# MainBoard.net
KiCad netlist of a schematic drawn in EAGLE
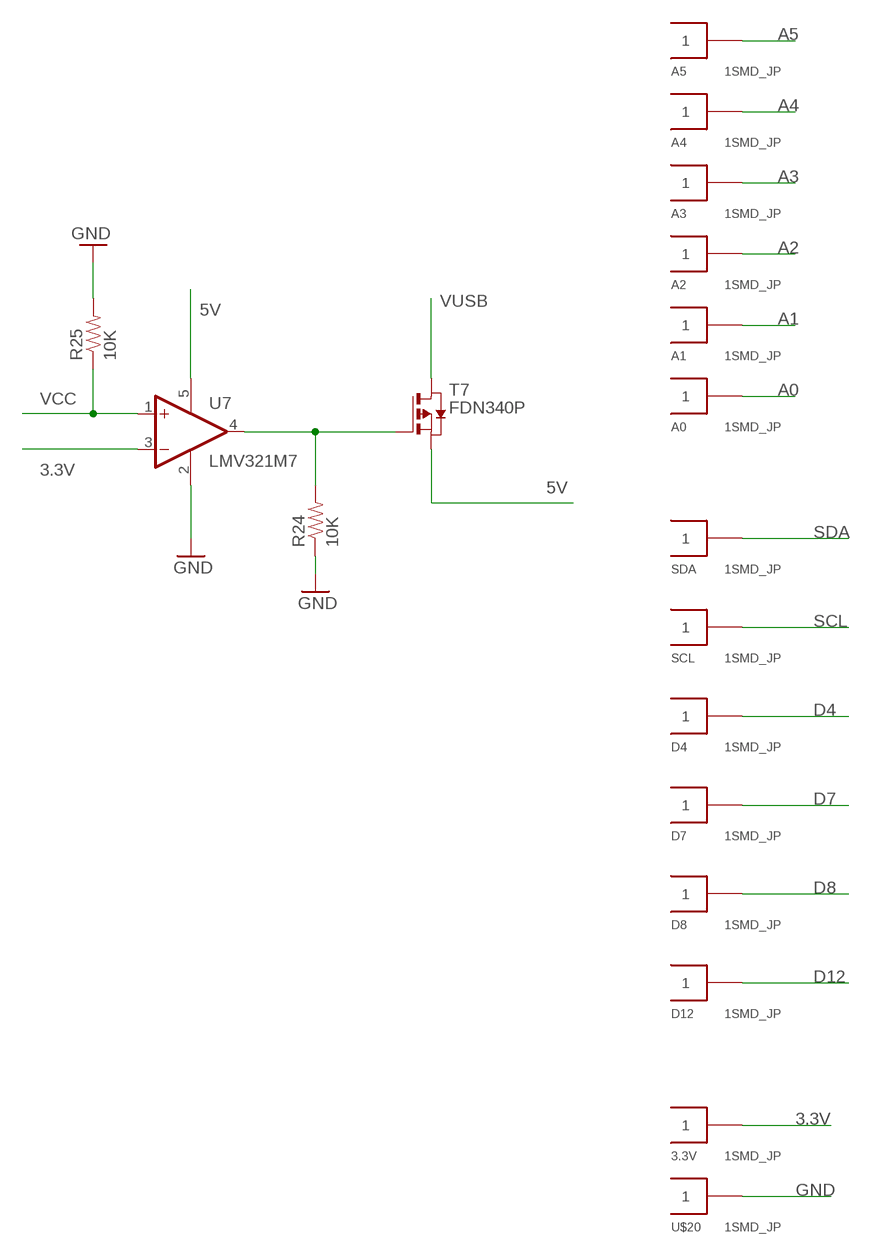
[diagram p0: schematic, sheet 1, part 1 of 2]
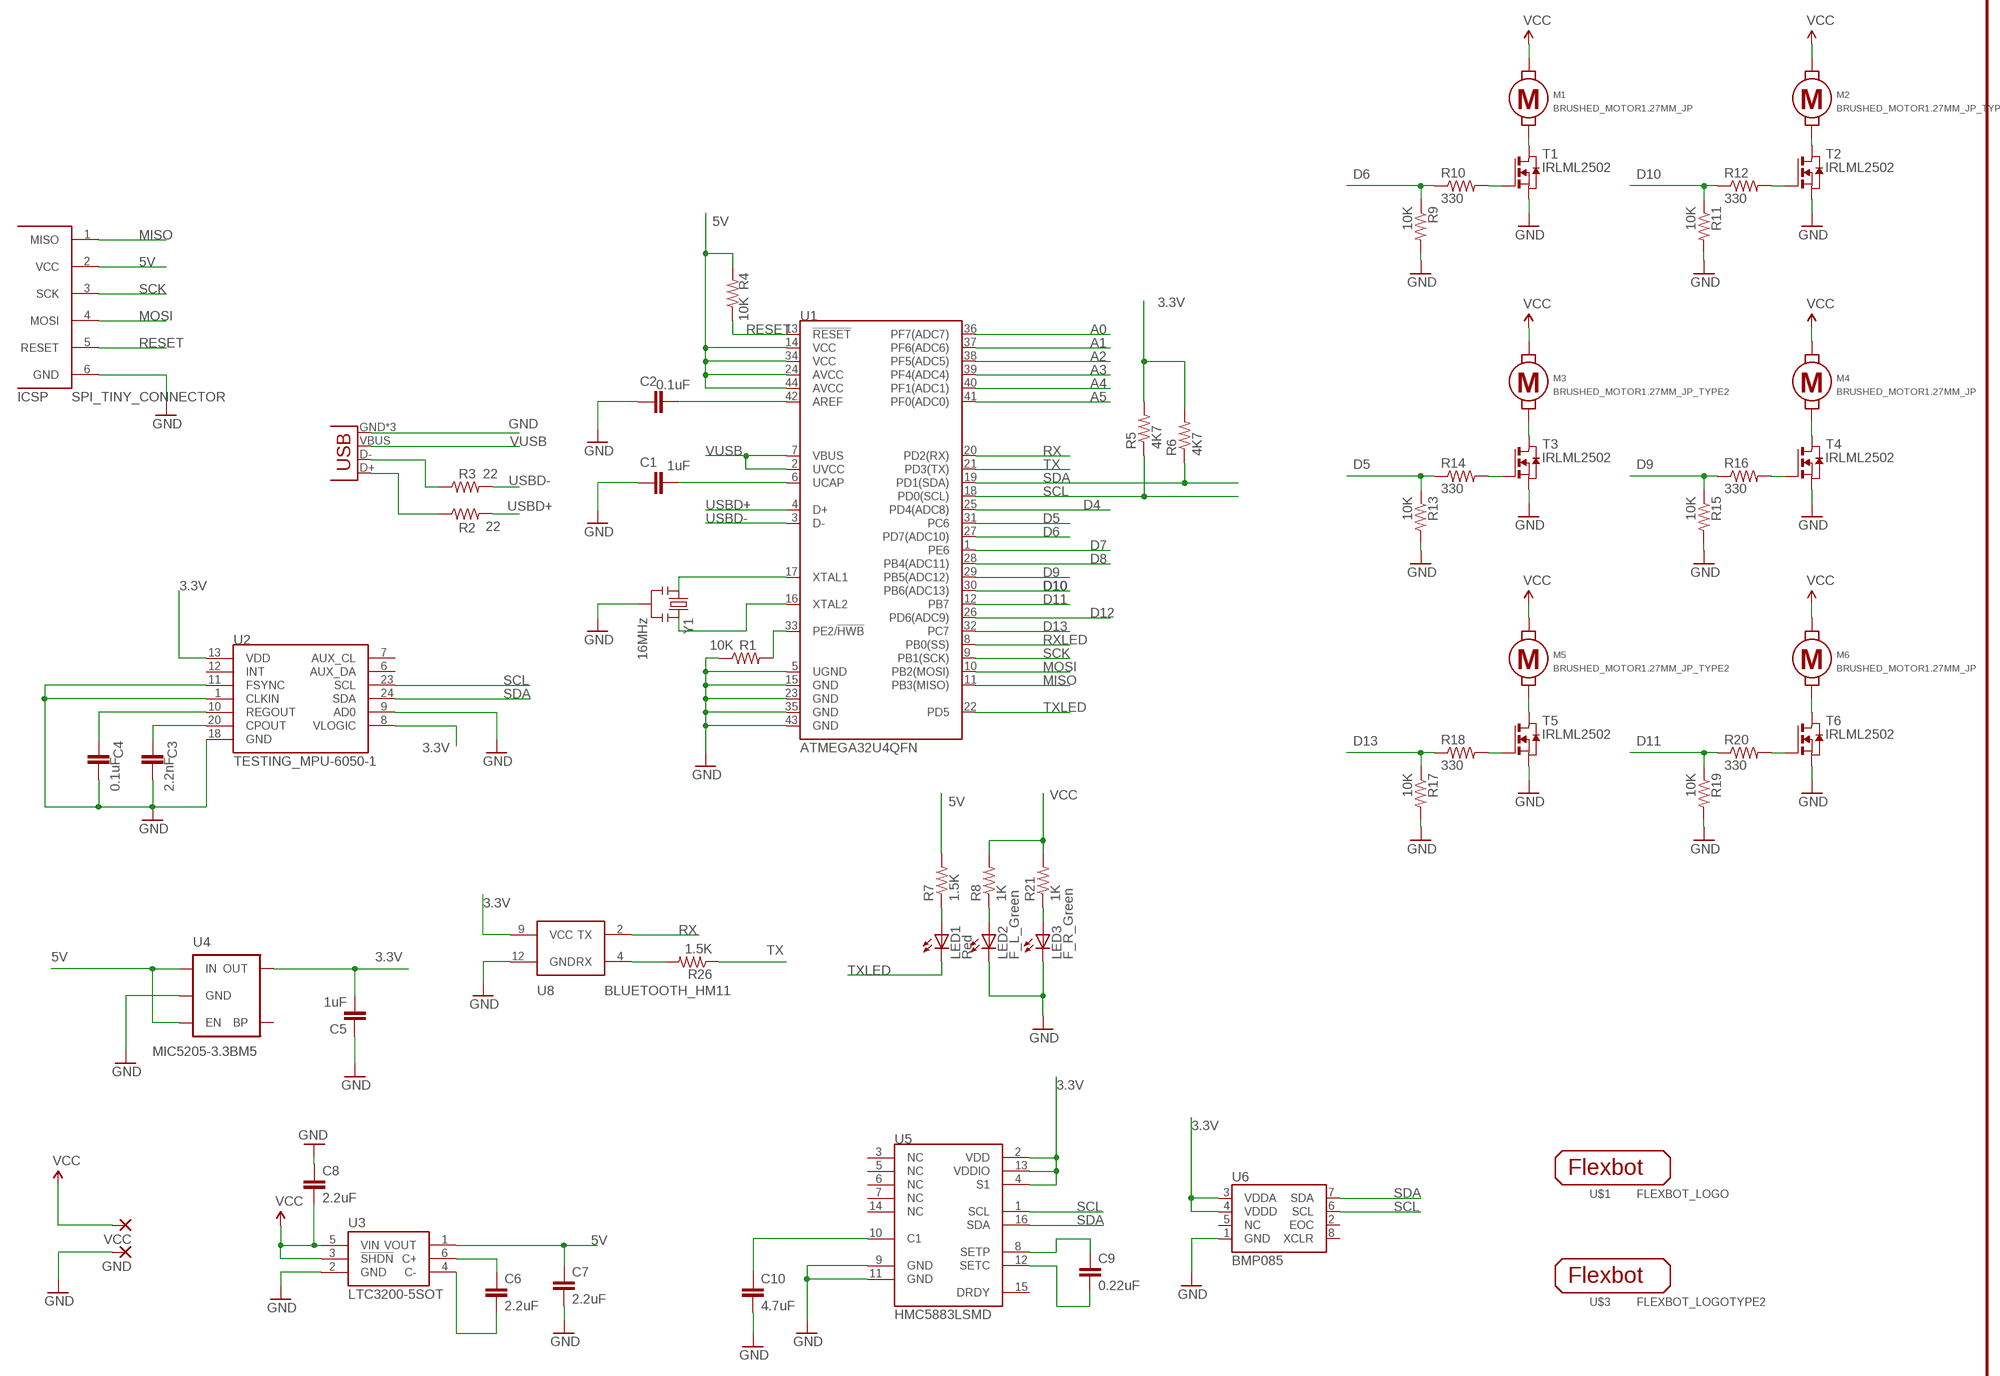
[diagram p1: schematic, sheet 1, part 2 of 2]

(export (version "E")
  (design (tool "Eeschema 10.0.6"))
  (components
    (comp (ref "3.3V")
      (value "1SMD_JP")
      (footprint "eagle-import:1SMD")
      (libsource (lib "eagle-import") (part "1SMD_JP"))
    )
    (comp (ref "A0")
      (value "1SMD_JP")
      (footprint "eagle-import:1SMD")
      (libsource (lib "eagle-import") (part "1SMD_JP"))
    )
    (comp (ref "A1")
      (value "1SMD_JP")
      (footprint "eagle-import:1SMD")
      (libsource (lib "eagle-import") (part "1SMD_JP"))
    )
    (comp (ref "A2")
      (value "1SMD_JP")
      (footprint "eagle-import:1SMD")
      (libsource (lib "eagle-import") (part "1SMD_JP"))
    )
    (comp (ref "A3")
      (value "1SMD_JP")
      (footprint "eagle-import:1SMD")
      (libsource (lib "eagle-import") (part "1SMD_JP"))
    )
    (comp (ref "A4")
      (value "1SMD_JP")
      (footprint "eagle-import:1SMD")
      (libsource (lib "eagle-import") (part "1SMD_JP"))
    )
    (comp (ref "A5")
      (value "1SMD_JP")
      (footprint "eagle-import:1SMD")
      (libsource (lib "eagle-import") (part "1SMD_JP"))
    )
    (comp (ref "C1")
      (value "1uF")
      (footprint "eagle-import:0402-CAP")
      (libsource (lib "eagle-import") (part "CAP0402-CAP"))
    )
    (comp (ref "C2")
      (value "0.1uF")
      (footprint "eagle-import:0402-CAP")
      (libsource (lib "eagle-import") (part "CAP0402-CAP"))
    )
    (comp (ref "C3")
      (value "2.2nF")
      (footprint "eagle-import:0402-CAP")
      (libsource (lib "eagle-import") (part "CAP0402-CAP"))
    )
    (comp (ref "C4")
      (value "0.1uF")
      (footprint "eagle-import:0402-CAP")
      (libsource (lib "eagle-import") (part "CAP0402-CAP"))
    )
    (comp (ref "C5")
      (value "1uF")
      (footprint "eagle-import:0402-CAP")
      (libsource (lib "eagle-import") (part "CAP0402-CAP"))
    )
    (comp (ref "C6")
      (value "2.2uF")
      (footprint "eagle-import:0603-CAP")
      (libsource (lib "eagle-import") (part "CAP0603-CAP"))
    )
    (comp (ref "C7")
      (value "2.2uF")
      (footprint "eagle-import:0603-CAP")
      (libsource (lib "eagle-import") (part "CAP0603-CAP"))
    )
    (comp (ref "C8")
      (value "2.2uF")
      (footprint "eagle-import:0603-CAP")
      (libsource (lib "eagle-import") (part "CAP0603-CAP"))
    )
    (comp (ref "C9")
      (value "0.22uF")
      (footprint "eagle-import:0402-CAP")
      (libsource (lib "eagle-import") (part "CAP0402-CAP"))
    )
    (comp (ref "C10")
      (value "4.7uF")
      (footprint "eagle-import:0603-CAP")
      (libsource (lib "eagle-import") (part "CAP0603-CAP"))
    )
    (comp (ref "D4")
      (value "1SMD_JP")
      (footprint "eagle-import:1SMD")
      (libsource (lib "eagle-import") (part "1SMD_JP"))
    )
    (comp (ref "D7")
      (value "1SMD_JP")
      (footprint "eagle-import:1SMD")
      (libsource (lib "eagle-import") (part "1SMD_JP"))
    )
    (comp (ref "D8")
      (value "1SMD_JP")
      (footprint "eagle-import:1SMD")
      (libsource (lib "eagle-import") (part "1SMD_JP"))
    )
    (comp (ref "D12")
      (value "1SMD_JP")
      (footprint "eagle-import:1SMD")
      (libsource (lib "eagle-import") (part "1SMD_JP"))
    )
    (comp (ref "GND")
      (value "2,15/1,0")
      (footprint "eagle-import:2,15_1,0")
      (libsource (lib "eagle-import") (part "2,15/1,0"))
    )
    (comp (ref "ICSP")
      (value "SPI_TINY_CONNECTOR")
      (footprint "eagle-import:AVR_ISP_TINY_CONNECTOR_NO_BORDER")
      (libsource (lib "eagle-import") (part "AVR_ISP_TINY_CONNECTORAVR_ISP_TINY_CONNCTOR_NO_BORDER"))
    )
    (comp (ref "JP1")
      (value "USB-MICROB")
      (footprint "eagle-import:USB-MICROB")
      (libsource (lib "eagle-import") (part "USB-MICROB"))
    )
    (comp (ref "LED1")
      (value "Red")
      (footprint "eagle-import:CHIPLED_0603")
      (libsource (lib "eagle-import") (part "LEDCHIPLED_0603"))
    )
    (comp (ref "LED2")
      (value "F_L_Green")
      (footprint "eagle-import:CHIPLED_0603")
      (libsource (lib "eagle-import") (part "LEDCHIPLED_0603"))
    )
    (comp (ref "LED3")
      (value "F_R_Green")
      (footprint "eagle-import:CHIPLED_0603")
      (libsource (lib "eagle-import") (part "LEDCHIPLED_0603"))
    )
    (comp (ref "M1")
      (value "BRUSHED_MOTOR1.27MM_JP")
      (footprint "eagle-import:BRUSHED_MOTOR_1.27MM_JP")
      (libsource (lib "eagle-import") (part "BRUSHED_MOTOR1.27MM_JP"))
    )
    (comp (ref "M2")
      (value "BRUSHED_MOTOR1.27MM_JP_TYPE2")
      (footprint "eagle-import:BRUSHED_MOTOR_1.27MM_JP_TYPE2")
      (libsource (lib "eagle-import") (part "BRUSHED_MOTOR1.27MM_JP_TYPE2"))
    )
    (comp (ref "M3")
      (value "BRUSHED_MOTOR1.27MM_JP_TYPE2")
      (footprint "eagle-import:BRUSHED_MOTOR_1.27MM_JP_TYPE2")
      (libsource (lib "eagle-import") (part "BRUSHED_MOTOR1.27MM_JP_TYPE2"))
    )
    (comp (ref "M4")
      (value "BRUSHED_MOTOR1.27MM_JP")
      (footprint "eagle-import:BRUSHED_MOTOR_1.27MM_JP")
      (libsource (lib "eagle-import") (part "BRUSHED_MOTOR1.27MM_JP"))
    )
    (comp (ref "M5")
      (value "BRUSHED_MOTOR1.27MM_JP_TYPE2")
      (footprint "eagle-import:BRUSHED_MOTOR_1.27MM_JP_TYPE2")
      (libsource (lib "eagle-import") (part "BRUSHED_MOTOR1.27MM_JP_TYPE2"))
    )
    (comp (ref "M6")
      (value "BRUSHED_MOTOR1.27MM_JP")
      (footprint "eagle-import:BRUSHED_MOTOR_1.27MM_JP")
      (libsource (lib "eagle-import") (part "BRUSHED_MOTOR1.27MM_JP"))
    )
    (comp (ref "R1")
      (value "10K")
      (footprint "eagle-import:0402-RES")
      (libsource (lib "eagle-import") (part "RESISTOR0402-RES"))
    )
    (comp (ref "R2")
      (value "22")
      (footprint "eagle-import:0402-RES")
      (libsource (lib "eagle-import") (part "RESISTOR0402-RES"))
    )
    (comp (ref "R3")
      (value "22")
      (footprint "eagle-import:0402-RES")
      (libsource (lib "eagle-import") (part "RESISTOR0402-RES"))
    )
    (comp (ref "R4")
      (value "10K")
      (footprint "eagle-import:0402-RES")
      (libsource (lib "eagle-import") (part "RESISTOR0402-RES"))
    )
    (comp (ref "R5")
      (value "4K7")
      (footprint "eagle-import:0402-RES")
      (libsource (lib "eagle-import") (part "RESISTOR0402-RES"))
    )
    (comp (ref "R6")
      (value "4K7")
      (footprint "eagle-import:0402-RES")
      (libsource (lib "eagle-import") (part "RESISTOR0402-RES"))
    )
    (comp (ref "R7")
      (value "1.5K")
      (footprint "eagle-import:0402-RES")
      (libsource (lib "eagle-import") (part "RESISTOR0402-RES"))
    )
    (comp (ref "R8")
      (value "1K")
      (footprint "eagle-import:0402-RES")
      (libsource (lib "eagle-import") (part "RESISTOR0402-RES"))
    )
    (comp (ref "R9")
      (value "10K")
      (footprint "eagle-import:0402-RES")
      (libsource (lib "eagle-import") (part "RESISTOR0402-RES"))
    )
    (comp (ref "R10")
      (value "330")
      (footprint "eagle-import:0402-RES")
      (libsource (lib "eagle-import") (part "RESISTOR0402-RES"))
    )
    (comp (ref "R11")
      (value "10K")
      (footprint "eagle-import:0402-RES")
      (libsource (lib "eagle-import") (part "RESISTOR0402-RES"))
    )
    (comp (ref "R12")
      (value "330")
      (footprint "eagle-import:0402-RES")
      (libsource (lib "eagle-import") (part "RESISTOR0402-RES"))
    )
    (comp (ref "R13")
      (value "10K")
      (footprint "eagle-import:0402-RES")
      (libsource (lib "eagle-import") (part "RESISTOR0402-RES"))
    )
    (comp (ref "R14")
      (value "330")
      (footprint "eagle-import:0402-RES")
      (libsource (lib "eagle-import") (part "RESISTOR0402-RES"))
    )
    (comp (ref "R15")
      (value "10K")
      (footprint "eagle-import:0402-RES")
      (libsource (lib "eagle-import") (part "RESISTOR0402-RES"))
    )
    (comp (ref "R16")
      (value "330")
      (footprint "eagle-import:0402-RES")
      (libsource (lib "eagle-import") (part "RESISTOR0402-RES"))
    )
    (comp (ref "R17")
      (value "10K")
      (footprint "eagle-import:0402-RES")
      (libsource (lib "eagle-import") (part "RESISTOR0402-RES"))
    )
    (comp (ref "R18")
      (value "330")
      (footprint "eagle-import:0402-RES")
      (libsource (lib "eagle-import") (part "RESISTOR0402-RES"))
    )
    (comp (ref "R19")
      (value "10K")
      (footprint "eagle-import:0402-RES")
      (libsource (lib "eagle-import") (part "RESISTOR0402-RES"))
    )
    (comp (ref "R20")
      (value "330")
      (footprint "eagle-import:0402-RES")
      (libsource (lib "eagle-import") (part "RESISTOR0402-RES"))
    )
    (comp (ref "R21")
      (value "1K")
      (footprint "eagle-import:0402-RES")
      (libsource (lib "eagle-import") (part "RESISTOR0402-RES"))
    )
    (comp (ref "R24")
      (value "10K")
      (footprint "eagle-import:0402-RES")
      (libsource (lib "eagle-import") (part "RESISTOR0402-RES"))
    )
    (comp (ref "R25")
      (value "10K")
      (footprint "eagle-import:0402-RES")
      (libsource (lib "eagle-import") (part "RESISTOR0402-RES"))
    )
    (comp (ref "R26")
      (value "1.5K")
      (footprint "eagle-import:0402-RES")
      (libsource (lib "eagle-import") (part "RESISTOR0402-RES"))
    )
    (comp (ref "SCL")
      (value "1SMD_JP")
      (footprint "eagle-import:1SMD")
      (libsource (lib "eagle-import") (part "1SMD_JP"))
    )
    (comp (ref "SDA")
      (value "1SMD_JP")
      (footprint "eagle-import:1SMD")
      (libsource (lib "eagle-import") (part "1SMD_JP"))
    )
    (comp (ref "T1")
      (value "IRLML2502")
      (footprint "eagle-import:SOT-23")
      (libsource (lib "eagle-import") (part "NMOSSOT23"))
    )
    (comp (ref "T2")
      (value "IRLML2502")
      (footprint "eagle-import:SOT-23")
      (libsource (lib "eagle-import") (part "NMOSSOT23"))
    )
    (comp (ref "T3")
      (value "IRLML2502")
      (footprint "eagle-import:SOT-23")
      (libsource (lib "eagle-import") (part "NMOSSOT23"))
    )
    (comp (ref "T4")
      (value "IRLML2502")
      (footprint "eagle-import:SOT-23")
      (libsource (lib "eagle-import") (part "NMOSSOT23"))
    )
    (comp (ref "T5")
      (value "IRLML2502")
      (footprint "eagle-import:SOT-23")
      (libsource (lib "eagle-import") (part "NMOSSOT23"))
    )
    (comp (ref "T6")
      (value "IRLML2502")
      (footprint "eagle-import:SOT-23")
      (libsource (lib "eagle-import") (part "NMOSSOT23"))
    )
    (comp (ref "T7")
      (value "FDN340P")
      (footprint "eagle-import:SOT23")
      (libsource (lib "eagle-import") (part "FDN340P"))
    )
    (comp (ref "U$1")
      (value "FLEXBOT_LOGO")
      (footprint "eagle-import:FLEXBOT_LOGO")
      (libsource (lib "eagle-import") (part "FLEXBOT_LOGO"))
    )
    (comp (ref "U$3")
      (value "FLEXBOT_LOGOTYPE2")
      (footprint "eagle-import:FLEXBOT_LOGO_TYPE2")
      (libsource (lib "eagle-import") (part "FLEXBOT_LOGOTYPE2"))
    )
    (comp (ref "U$20")
      (value "1SMD_JP")
      (footprint "eagle-import:1SMD")
      (libsource (lib "eagle-import") (part "1SMD_JP"))
    )
    (comp (ref "U1")
      (value "ATMEGA32U4QFN")
      (footprint "eagle-import:SPARKFUN-DIGITALIC_QFN-44")
      (libsource (lib "eagle-import") (part "ATMEGA32U4QFN"))
    )
    (comp (ref "U2")
      (value "TESTING_MPU-6050-1")
      (footprint "eagle-import:TESTING_QFN-24-4MM2")
      (libsource (lib "eagle-import") (part "TESTING_MPU-6050-1"))
    )
    (comp (ref "U3")
      (value "LTC3200-5SOT")
      (footprint "eagle-import:SOT23-6")
      (libsource (lib "eagle-import") (part "LTC3200-5SOT"))
    )
    (comp (ref "U4")
      (value "MIC5205-3.3BM5")
      (footprint "eagle-import:SOT23-5")
      (libsource (lib "eagle-import") (part "MIC52053.3V"))
    )
    (comp (ref "U5")
      (value "HMC5883LSMD")
      (footprint "eagle-import:16LPCC")
      (libsource (lib "eagle-import") (part "HMC5883LSMD"))
    )
    (comp (ref "U6")
      (value "BMP085")
      (footprint "eagle-import:BMP085")
      (libsource (lib "eagle-import") (part "BMP085"))
    )
    (comp (ref "U7")
      (value "LMV321M7")
      (footprint "eagle-import:SC70-5L")
      (libsource (lib "eagle-import") (part "LMV321?M7"))
    )
    (comp (ref "U8")
      (value "BLUETOOTH_HM11")
      (footprint "eagle-import:BLUETOOTH_HM11")
      (libsource (lib "eagle-import") (part "BLUETOOTH_HM11"))
    )
    (comp (ref "VCC")
      (value "2,15/1,0")
      (footprint "eagle-import:2,15_1,0")
      (libsource (lib "eagle-import") (part "2,15/1,0"))
    )
    (comp (ref "Y1")
      (value "16MHz")
      (footprint "eagle-import:RESONATOR-SMD")
      (libsource (lib "eagle-import") (part "RESONATOR16MHZ"))
    )
  )
  (nets
    (net (code "1") (name "/3.3V") (class "Default")
      (node (ref "3.3V") (pin "1") (pinfunction "1_1") (pintype "bidirectional"))
      (node (ref "C5") (pin "2") (pinfunction "2_2") (pintype "passive"))
      (node (ref "R5") (pin "2") (pinfunction "2_2") (pintype "passive"))
      (node (ref "R6") (pin "2") (pinfunction "2_2") (pintype "passive"))
      (node (ref "U2") (pin "13") (pinfunction "VDD_13") (pintype "bidirectional"))
      (node (ref "U2") (pin "8") (pinfunction "VLOGIC_8") (pintype "bidirectional"))
      (node (ref "U4") (pin "5") (pinfunction "OUT_5") (pintype "passive"))
      (node (ref "U5") (pin "13") (pinfunction "VDDIO_13") (pintype "bidirectional"))
      (node (ref "U5") (pin "2") (pinfunction "VDD_2") (pintype "bidirectional"))
      (node (ref "U5") (pin "4") (pinfunction "S1_4") (pintype "bidirectional"))
      (node (ref "U6") (pin "3") (pinfunction "VDDA_3") (pintype "power_in"))
      (node (ref "U6") (pin "4") (pinfunction "VDDD_4") (pintype "power_in"))
      (node (ref "U7") (pin "3") (pinfunction "-IN_3") (pintype "input"))
      (node (ref "U8") (pin "9") (pinfunction "VCC_9") (pintype "bidirectional"))
    )
    (net (code "2") (name "/5V") (class "Default")
      (node (ref "C7") (pin "1") (pinfunction "1_1") (pintype "passive"))
      (node (ref "ICSP") (pin "2") (pinfunction "VCC_2") (pintype "bidirectional"))
      (node (ref "R4") (pin "2") (pinfunction "2_2") (pintype "passive"))
      (node (ref "R7") (pin "2") (pinfunction "2_2") (pintype "passive"))
      (node (ref "T7") (pin "2") (pinfunction "S_2") (pintype "passive"))
      (node (ref "U1") (pin "14") (pinfunction "VCC_14") (pintype "bidirectional"))
      (node (ref "U1") (pin "24") (pinfunction "AVCC_24") (pintype "bidirectional"))
      (node (ref "U1") (pin "34") (pinfunction "VCC_34") (pintype "bidirectional"))
      (node (ref "U1") (pin "44") (pinfunction "AVCC_44") (pintype "bidirectional"))
      (node (ref "U3") (pin "1") (pinfunction "VOUT_1") (pintype "bidirectional"))
      (node (ref "U4") (pin "1") (pinfunction "IN_1") (pintype "input"))
      (node (ref "U4") (pin "3") (pinfunction "EN_3") (pintype "input"))
      (node (ref "U7") (pin "5") (pinfunction "V+_5") (pintype "power_in"))
    )
    (net (code "3") (name "/A0") (class "Default")
      (node (ref "A0") (pin "1") (pinfunction "1_1") (pintype "bidirectional"))
      (node (ref "U1") (pin "36") (pinfunction "PF7(ADC7)_36") (pintype "bidirectional"))
    )
    (net (code "4") (name "/A1") (class "Default")
      (node (ref "A1") (pin "1") (pinfunction "1_1") (pintype "bidirectional"))
      (node (ref "U1") (pin "37") (pinfunction "PF6(ADC6)_37") (pintype "bidirectional"))
    )
    (net (code "5") (name "/A2") (class "Default")
      (node (ref "A2") (pin "1") (pinfunction "1_1") (pintype "bidirectional"))
      (node (ref "U1") (pin "38") (pinfunction "PF5(ADC5)_38") (pintype "bidirectional"))
    )
    (net (code "6") (name "/A3") (class "Default")
      (node (ref "A3") (pin "1") (pinfunction "1_1") (pintype "bidirectional"))
      (node (ref "U1") (pin "39") (pinfunction "PF4(ADC4)_39") (pintype "bidirectional"))
    )
    (net (code "7") (name "/A4") (class "Default")
      (node (ref "A4") (pin "1") (pinfunction "1_1") (pintype "bidirectional"))
      (node (ref "U1") (pin "40") (pinfunction "PF1(ADC1)_40") (pintype "bidirectional"))
    )
    (net (code "8") (name "/A5") (class "Default")
      (node (ref "A5") (pin "1") (pinfunction "1_1") (pintype "bidirectional"))
      (node (ref "U1") (pin "41") (pinfunction "PF0(ADC0)_41") (pintype "bidirectional"))
    )
    (net (code "9") (name "/D4") (class "Default")
      (node (ref "D4") (pin "1") (pinfunction "1_1") (pintype "bidirectional"))
      (node (ref "U1") (pin "25") (pinfunction "PD4(ADC8)_25") (pintype "bidirectional"))
    )
    (net (code "10") (name "/D5") (class "Default")
      (node (ref "R13") (pin "1") (pinfunction "1_1") (pintype "passive"))
      (node (ref "R14") (pin "1") (pinfunction "1_1") (pintype "passive"))
      (node (ref "U1") (pin "31") (pinfunction "PC6_31") (pintype "bidirectional"))
    )
    (net (code "11") (name "/D6") (class "Default")
      (node (ref "R10") (pin "1") (pinfunction "1_1") (pintype "passive"))
      (node (ref "R9") (pin "1") (pinfunction "1_1") (pintype "passive"))
      (node (ref "U1") (pin "27") (pinfunction "PD7(ADC10)_27") (pintype "bidirectional"))
    )
    (net (code "12") (name "/D7") (class "Default")
      (node (ref "D7") (pin "1") (pinfunction "1_1") (pintype "bidirectional"))
      (node (ref "U1") (pin "1") (pinfunction "PE6_1") (pintype "bidirectional"))
    )
    (net (code "13") (name "/D8") (class "Default")
      (node (ref "D8") (pin "1") (pinfunction "1_1") (pintype "bidirectional"))
      (node (ref "U1") (pin "28") (pinfunction "PB4(ADC11)_28") (pintype "bidirectional"))
    )
    (net (code "14") (name "/D9") (class "Default")
      (node (ref "R15") (pin "1") (pinfunction "1_1") (pintype "passive"))
      (node (ref "R16") (pin "1") (pinfunction "1_1") (pintype "passive"))
      (node (ref "U1") (pin "29") (pinfunction "PB5(ADC12)_29") (pintype "bidirectional"))
    )
    (net (code "15") (name "/D10") (class "Default")
      (node (ref "R11") (pin "1") (pinfunction "1_1") (pintype "passive"))
      (node (ref "R12") (pin "1") (pinfunction "1_1") (pintype "passive"))
      (node (ref "U1") (pin "30") (pinfunction "PB6(ADC13)_30") (pintype "bidirectional"))
    )
    (net (code "16") (name "/D11") (class "Default")
      (node (ref "R19") (pin "1") (pinfunction "1_1") (pintype "passive"))
      (node (ref "R20") (pin "1") (pinfunction "1_1") (pintype "passive"))
      (node (ref "U1") (pin "12") (pinfunction "PB7_12") (pintype "bidirectional"))
    )
    (net (code "17") (name "/D12") (class "Default")
      (node (ref "D12") (pin "1") (pinfunction "1_1") (pintype "bidirectional"))
      (node (ref "U1") (pin "26") (pinfunction "PD6(ADC9)_26") (pintype "bidirectional"))
    )
    (net (code "18") (name "/D13") (class "Default")
      (node (ref "R17") (pin "1") (pinfunction "1_1") (pintype "passive"))
      (node (ref "R18") (pin "1") (pinfunction "1_1") (pintype "passive"))
      (node (ref "U1") (pin "32") (pinfunction "PC7_32") (pintype "bidirectional"))
    )
    (net (code "19") (name "/MISO") (class "Default")
      (node (ref "ICSP") (pin "1") (pinfunction "MISO_1") (pintype "bidirectional"))
      (node (ref "U1") (pin "11") (pinfunction "PB3(MISO)_11") (pintype "bidirectional"))
    )
    (net (code "20") (name "/MOSI") (class "Default")
      (node (ref "ICSP") (pin "4") (pinfunction "MOSI_4") (pintype "bidirectional"))
      (node (ref "U1") (pin "10") (pinfunction "PB2(MOSI)_10") (pintype "bidirectional"))
    )
    (net (code "21") (name "/RESET") (class "Default")
      (node (ref "ICSP") (pin "5") (pinfunction "RESET_5") (pintype "bidirectional"))
      (node (ref "R4") (pin "1") (pinfunction "1_1") (pintype "passive"))
      (node (ref "U1") (pin "13") (pinfunction "~{RESET}_13") (pintype "bidirectional"))
    )
    (net (code "22") (name "/RX") (class "Default")
      (node (ref "U1") (pin "20") (pinfunction "PD2(RX)_20") (pintype "bidirectional"))
      (node (ref "U8") (pin "2") (pinfunction "TX_2") (pintype "bidirectional"))
    )
    (net (code "23") (name "/RXLED") (class "Default")
      (node (ref "U1") (pin "8") (pinfunction "PB0(SS)_8") (pintype "bidirectional"))
    )
    (net (code "24") (name "/SCK") (class "Default")
      (node (ref "ICSP") (pin "3") (pinfunction "SCK_3") (pintype "bidirectional"))
      (node (ref "U1") (pin "9") (pinfunction "PB1(SCK)_9") (pintype "bidirectional"))
    )
    (net (code "25") (name "/SCL") (class "Default")
      (node (ref "R5") (pin "1") (pinfunction "1_1") (pintype "passive"))
      (node (ref "SCL") (pin "1") (pinfunction "1_1") (pintype "bidirectional"))
      (node (ref "U1") (pin "18") (pinfunction "PD0(SCL)_18") (pintype "bidirectional"))
      (node (ref "U2") (pin "23") (pinfunction "SCL_23") (pintype "bidirectional"))
      (node (ref "U5") (pin "1") (pinfunction "SCL_1") (pintype "bidirectional"))
      (node (ref "U6") (pin "6") (pinfunction "SCL_6") (pintype "input"))
    )
    (net (code "26") (name "/SDA") (class "Default")
      (node (ref "R6") (pin "1") (pinfunction "1_1") (pintype "passive"))
      (node (ref "SDA") (pin "1") (pinfunction "1_1") (pintype "bidirectional"))
      (node (ref "U1") (pin "19") (pinfunction "PD1(SDA)_19") (pintype "bidirectional"))
      (node (ref "U2") (pin "24") (pinfunction "SDA_24") (pintype "bidirectional"))
      (node (ref "U5") (pin "16") (pinfunction "SDA_16") (pintype "bidirectional"))
      (node (ref "U6") (pin "7") (pinfunction "SDA_7") (pintype "bidirectional"))
    )
    (net (code "27") (name "/TX") (class "Default")
      (node (ref "R26") (pin "1") (pinfunction "1_1") (pintype "passive"))
      (node (ref "U1") (pin "21") (pinfunction "PD3(TX)_21") (pintype "bidirectional"))
    )
    (net (code "28") (name "/TXLED") (class "Default")
      (node (ref "LED1") (pin "C") (pinfunction "C_C") (pintype "passive"))
      (node (ref "U1") (pin "22") (pinfunction "PD5_22") (pintype "bidirectional"))
    )
    (net (code "29") (name "/USBD+") (class "Default")
      (node (ref "R2") (pin "2") (pinfunction "2_2") (pintype "passive"))
      (node (ref "U1") (pin "4") (pinfunction "D+_4") (pintype "bidirectional"))
    )
    (net (code "30") (name "/USBD-") (class "Default")
      (node (ref "R3") (pin "2") (pinfunction "2_2") (pintype "passive"))
      (node (ref "U1") (pin "3") (pinfunction "D-_3") (pintype "bidirectional"))
    )
    (net (code "31") (name "/VUSB") (class "Default")
      (node (ref "JP1") (pin "VBUS") (pinfunction "VBUS_VBUS") (pintype "bidirectional"))
      (node (ref "T7") (pin "1") (pinfunction "D_1") (pintype "passive"))
      (node (ref "U1") (pin "2") (pinfunction "UVCC_2") (pintype "bidirectional"))
      (node (ref "U1") (pin "7") (pinfunction "VBUS_7") (pintype "bidirectional"))
    )
    (net (code "32") (name "GND") (class "Default")
      (node (ref "C1") (pin "1") (pinfunction "1_1") (pintype "passive"))
      (node (ref "C10") (pin "2") (pinfunction "2_2") (pintype "passive"))
      (node (ref "C2") (pin "1") (pinfunction "1_1") (pintype "passive"))
      (node (ref "C3") (pin "2") (pinfunction "2_2") (pintype "passive"))
      (node (ref "C4") (pin "2") (pinfunction "2_2") (pintype "passive"))
      (node (ref "C5") (pin "1") (pinfunction "1_1") (pintype "passive"))
      (node (ref "C7") (pin "2") (pinfunction "2_2") (pintype "passive"))
      (node (ref "C8") (pin "1") (pinfunction "1_1") (pintype "passive"))
      (node (ref "GND") (pin "1") (pinfunction "P_1") (pintype "passive"))
      (node (ref "ICSP") (pin "6") (pinfunction "GND_6") (pintype "bidirectional"))
      (node (ref "JP1") (pin "GND") (pinfunction "GND_GND") (pintype "bidirectional"))
      (node (ref "JP1") (pin "MT1") (pinfunction "GND_MT1") (pintype "bidirectional"))
      (node (ref "JP1") (pin "MT2") (pinfunction "GND_MT2") (pintype "bidirectional"))
      (node (ref "LED2") (pin "C") (pinfunction "C_C") (pintype "passive"))
      (node (ref "LED3") (pin "C") (pinfunction "C_C") (pintype "passive"))
      (node (ref "R1") (pin "1") (pinfunction "1_1") (pintype "passive"))
      (node (ref "R11") (pin "2") (pinfunction "2_2") (pintype "passive"))
      (node (ref "R13") (pin "2") (pinfunction "2_2") (pintype "passive"))
      (node (ref "R15") (pin "2") (pinfunction "2_2") (pintype "passive"))
      (node (ref "R17") (pin "2") (pinfunction "2_2") (pintype "passive"))
      (node (ref "R19") (pin "2") (pinfunction "2_2") (pintype "passive"))
      (node (ref "R24") (pin "1") (pinfunction "1_1") (pintype "passive"))
      (node (ref "R25") (pin "2") (pinfunction "2_2") (pintype "passive"))
      (node (ref "R9") (pin "2") (pinfunction "2_2") (pintype "passive"))
      (node (ref "T1") (pin "2") (pinfunction "S_2") (pintype "passive"))
      (node (ref "T2") (pin "2") (pinfunction "S_2") (pintype "passive"))
      (node (ref "T3") (pin "2") (pinfunction "S_2") (pintype "passive"))
      (node (ref "T4") (pin "2") (pinfunction "S_2") (pintype "passive"))
      (node (ref "T5") (pin "2") (pinfunction "S_2") (pintype "passive"))
      (node (ref "T6") (pin "2") (pinfunction "S_2") (pintype "passive"))
      (node (ref "U$20") (pin "1") (pinfunction "1_1") (pintype "bidirectional"))
      (node (ref "U1") (pin "15") (pinfunction "GND_15") (pintype "bidirectional"))
      (node (ref "U1") (pin "23") (pinfunction "GND_23") (pintype "bidirectional"))
      (node (ref "U1") (pin "35") (pinfunction "GND_35") (pintype "bidirectional"))
      (node (ref "U1") (pin "43") (pinfunction "GND_43") (pintype "bidirectional"))
      (node (ref "U1") (pin "5") (pinfunction "UGND_5") (pintype "bidirectional"))
      (node (ref "U2") (pin "1") (pinfunction "CLKIN_1") (pintype "bidirectional"))
      (node (ref "U2") (pin "11") (pinfunction "FSYNC_11") (pintype "bidirectional"))
      (node (ref "U2") (pin "18") (pinfunction "GND_18") (pintype "bidirectional"))
      (node (ref "U2") (pin "9") (pinfunction "AD0_9") (pintype "bidirectional"))
      (node (ref "U3") (pin "2") (pinfunction "GND_2") (pintype "bidirectional"))
      (node (ref "U4") (pin "2") (pinfunction "GND_2") (pintype "input"))
      (node (ref "U5") (pin "11") (pinfunction "GND_11") (pintype "bidirectional"))
      (node (ref "U5") (pin "9") (pinfunction "GND_9") (pintype "bidirectional"))
      (node (ref "U6") (pin "1") (pinfunction "GND_1") (pintype "power_in"))
      (node (ref "U7") (pin "2") (pinfunction "V-_2") (pintype "power_in"))
      (node (ref "U8") (pin "12") (pinfunction "GND_12") (pintype "bidirectional"))
      (node (ref "Y1") (pin "2") (pinfunction "2_2") (pintype "passive"))
    )
    (net (code "33") (name "Net-(JP1-PadD+)") (class "Default")
      (node (ref "JP1") (pin "D+") (pinfunction "D+_D+") (pintype "bidirectional"))
      (node (ref "R2") (pin "1") (pinfunction "1_1") (pintype "passive"))
    )
    (net (code "34") (name "Net-(JP1-PadD-)") (class "Default")
      (node (ref "JP1") (pin "D-") (pinfunction "D-_D-") (pintype "bidirectional"))
      (node (ref "R3") (pin "1") (pinfunction "1_1") (pintype "passive"))
    )
    (net (code "35") (name "Net-(LED1-PadA)") (class "Default")
      (node (ref "LED1") (pin "A") (pinfunction "A_A") (pintype "passive"))
      (node (ref "R7") (pin "1") (pinfunction "1_1") (pintype "passive"))
    )
    (net (code "36") (name "Net-(LED2-PadA)") (class "Default")
      (node (ref "LED2") (pin "A") (pinfunction "A_A") (pintype "passive"))
      (node (ref "R8") (pin "1") (pinfunction "1_1") (pintype "passive"))
    )
    (net (code "37") (name "Net-(LED3-PadA)") (class "Default")
      (node (ref "LED3") (pin "A") (pinfunction "A_A") (pintype "passive"))
      (node (ref "R21") (pin "1") (pinfunction "1_1") (pintype "passive"))
    )
    (net (code "38") (name "Net-(M1-1)") (class "Default")
      (node (ref "M1") (pin "P$1") (pinfunction "1_P$1") (pintype "bidirectional"))
      (node (ref "T1") (pin "1") (pinfunction "D_1") (pintype "passive"))
    )
    (net (code "39") (name "Net-(M2-1)") (class "Default")
      (node (ref "M2") (pin "P$1") (pinfunction "1_P$1") (pintype "bidirectional"))
      (node (ref "T2") (pin "1") (pinfunction "D_1") (pintype "passive"))
    )
    (net (code "40") (name "Net-(M3-1)") (class "Default")
      (node (ref "M3") (pin "P$1") (pinfunction "1_P$1") (pintype "bidirectional"))
      (node (ref "T3") (pin "1") (pinfunction "D_1") (pintype "passive"))
    )
    (net (code "41") (name "Net-(M4-1)") (class "Default")
      (node (ref "M4") (pin "P$1") (pinfunction "1_P$1") (pintype "bidirectional"))
      (node (ref "T4") (pin "1") (pinfunction "D_1") (pintype "passive"))
    )
    (net (code "42") (name "Net-(M5-1)") (class "Default")
      (node (ref "M5") (pin "P$1") (pinfunction "1_P$1") (pintype "bidirectional"))
      (node (ref "T5") (pin "1") (pinfunction "D_1") (pintype "passive"))
    )
    (net (code "43") (name "Net-(M6-1)") (class "Default")
      (node (ref "M6") (pin "P$1") (pinfunction "1_P$1") (pintype "bidirectional"))
      (node (ref "T6") (pin "1") (pinfunction "D_1") (pintype "passive"))
    )
    (net (code "44") (name "Net-(T1-G)") (class "Default")
      (node (ref "R10") (pin "2") (pinfunction "2_2") (pintype "passive"))
      (node (ref "T1") (pin "3") (pinfunction "G_3") (pintype "passive"))
    )
    (net (code "45") (name "Net-(T2-G)") (class "Default")
      (node (ref "R12") (pin "2") (pinfunction "2_2") (pintype "passive"))
      (node (ref "T2") (pin "3") (pinfunction "G_3") (pintype "passive"))
    )
    (net (code "46") (name "Net-(T3-G)") (class "Default")
      (node (ref "R14") (pin "2") (pinfunction "2_2") (pintype "passive"))
      (node (ref "T3") (pin "3") (pinfunction "G_3") (pintype "passive"))
    )
    (net (code "47") (name "Net-(T4-G)") (class "Default")
      (node (ref "R16") (pin "2") (pinfunction "2_2") (pintype "passive"))
      (node (ref "T4") (pin "3") (pinfunction "G_3") (pintype "passive"))
    )
    (net (code "48") (name "Net-(T5-G)") (class "Default")
      (node (ref "R18") (pin "2") (pinfunction "2_2") (pintype "passive"))
      (node (ref "T5") (pin "3") (pinfunction "G_3") (pintype "passive"))
    )
    (net (code "49") (name "Net-(T6-G)") (class "Default")
      (node (ref "R20") (pin "2") (pinfunction "2_2") (pintype "passive"))
      (node (ref "T6") (pin "3") (pinfunction "G_3") (pintype "passive"))
    )
    (net (code "50") (name "Net-(T7-G)") (class "Default")
      (node (ref "R24") (pin "2") (pinfunction "2_2") (pintype "passive"))
      (node (ref "T7") (pin "3") (pinfunction "G_3") (pintype "passive"))
      (node (ref "U7") (pin "4") (pinfunction "OUT_4") (pintype "output"))
    )
    (net (code "51") (name "Net-(U1-AREF)") (class "Default")
      (node (ref "C2") (pin "2") (pinfunction "2_2") (pintype "passive"))
      (node (ref "U1") (pin "42") (pinfunction "AREF_42") (pintype "bidirectional"))
    )
    (net (code "52") (name "Net-(U1-PE2{slash}~{HWB})") (class "Default")
      (node (ref "R1") (pin "2") (pinfunction "2_2") (pintype "passive"))
      (node (ref "U1") (pin "33") (pinfunction "PE2/~{HWB}_33") (pintype "bidirectional"))
    )
    (net (code "53") (name "Net-(U1-UCAP)") (class "Default")
      (node (ref "C1") (pin "2") (pinfunction "2_2") (pintype "passive"))
      (node (ref "U1") (pin "6") (pinfunction "UCAP_6") (pintype "bidirectional"))
    )
    (net (code "54") (name "Net-(U1-XTAL1)") (class "Default")
      (node (ref "U1") (pin "17") (pinfunction "XTAL1_17") (pintype "bidirectional"))
      (node (ref "Y1") (pin "1") (pinfunction "1_1") (pintype "passive"))
    )
    (net (code "55") (name "Net-(U1-XTAL2)") (class "Default")
      (node (ref "U1") (pin "16") (pinfunction "XTAL2_16") (pintype "bidirectional"))
      (node (ref "Y1") (pin "3") (pinfunction "3_3") (pintype "passive"))
    )
    (net (code "56") (name "Net-(U2-CPOUT)") (class "Default")
      (node (ref "C3") (pin "1") (pinfunction "1_1") (pintype "passive"))
      (node (ref "U2") (pin "20") (pinfunction "CPOUT_20") (pintype "bidirectional"))
    )
    (net (code "57") (name "Net-(U2-REGOUT)") (class "Default")
      (node (ref "C4") (pin "1") (pinfunction "1_1") (pintype "passive"))
      (node (ref "U2") (pin "10") (pinfunction "REGOUT_10") (pintype "bidirectional"))
    )
    (net (code "58") (name "Net-(U3-C+)") (class "Default")
      (node (ref "C6") (pin "1") (pinfunction "1_1") (pintype "passive"))
      (node (ref "U3") (pin "6") (pinfunction "C+_6") (pintype "bidirectional"))
    )
    (net (code "59") (name "Net-(U3-C-)") (class "Default")
      (node (ref "C6") (pin "2") (pinfunction "2_2") (pintype "passive"))
      (node (ref "U3") (pin "4") (pinfunction "C-_4") (pintype "bidirectional"))
    )
    (net (code "60") (name "Net-(U5-C1)") (class "Default")
      (node (ref "C10") (pin "1") (pinfunction "1_1") (pintype "passive"))
      (node (ref "U5") (pin "10") (pinfunction "C1_10") (pintype "bidirectional"))
    )
    (net (code "61") (name "Net-(U5-SETC)") (class "Default")
      (node (ref "C9") (pin "2") (pinfunction "2_2") (pintype "passive"))
      (node (ref "U5") (pin "12") (pinfunction "SETC_12") (pintype "bidirectional"))
    )
    (net (code "62") (name "Net-(U5-SETP)") (class "Default")
      (node (ref "C9") (pin "1") (pinfunction "1_1") (pintype "passive"))
      (node (ref "U5") (pin "8") (pinfunction "SETP_8") (pintype "bidirectional"))
    )
    (net (code "63") (name "Net-(U8-RX)") (class "Default")
      (node (ref "R26") (pin "2") (pinfunction "2_2") (pintype "passive"))
      (node (ref "U8") (pin "4") (pinfunction "RX_4") (pintype "bidirectional"))
    )
    (net (code "64") (name "VCC") (class "Default")
      (node (ref "C8") (pin "2") (pinfunction "2_2") (pintype "passive"))
      (node (ref "M1") (pin "P$2") (pinfunction "2_P$2") (pintype "bidirectional"))
      (node (ref "M2") (pin "P$2") (pinfunction "2_P$2") (pintype "bidirectional"))
      (node (ref "M3") (pin "P$2") (pinfunction "2_P$2") (pintype "bidirectional"))
      (node (ref "M4") (pin "P$2") (pinfunction "2_P$2") (pintype "bidirectional"))
      (node (ref "M5") (pin "P$2") (pinfunction "2_P$2") (pintype "bidirectional"))
      (node (ref "M6") (pin "P$2") (pinfunction "2_P$2") (pintype "bidirectional"))
      (node (ref "R21") (pin "2") (pinfunction "2_2") (pintype "passive"))
      (node (ref "R25") (pin "1") (pinfunction "1_1") (pintype "passive"))
      (node (ref "R8") (pin "2") (pinfunction "2_2") (pintype "passive"))
      (node (ref "U3") (pin "3") (pinfunction "~{SHDN}_3") (pintype "bidirectional"))
      (node (ref "U3") (pin "5") (pinfunction "VIN_5") (pintype "bidirectional"))
      (node (ref "U7") (pin "1") (pinfunction "+IN_1") (pintype "input"))
      (node (ref "VCC") (pin "1") (pinfunction "P_1") (pintype "passive"))
    )
    (net (code "65") (name "unconnected-(U2-AUX_CL-Pad7)") (class "Default")
      (node (ref "U2") (pin "7") (pinfunction "AUX_CL_7") (pintype "bidirectional"))
    )
    (net (code "66") (name "unconnected-(U2-AUX_DA-Pad6)") (class "Default")
      (node (ref "U2") (pin "6") (pinfunction "AUX_DA_6") (pintype "bidirectional"))
    )
    (net (code "67") (name "unconnected-(U2-INT-Pad12)") (class "Default")
      (node (ref "U2") (pin "12") (pinfunction "INT_12") (pintype "bidirectional"))
    )
    (net (code "68") (name "unconnected-(U4-BP-Pad4)") (class "Default")
      (node (ref "U4") (pin "4") (pinfunction "BP_4") (pintype "input"))
    )
    (net (code "69") (name "unconnected-(U5-DRDY-Pad15)") (class "Default")
      (node (ref "U5") (pin "15") (pinfunction "DRDY_15") (pintype "bidirectional"))
    )
    (net (code "70") (name "unconnected-(U5-NC-Pad3)") (class "Default")
      (node (ref "U5") (pin "3") (pinfunction "NC_3") (pintype "bidirectional"))
    )
    (net (code "71") (name "unconnected-(U5-NC-Pad5)") (class "Default")
      (node (ref "U5") (pin "5") (pinfunction "NC_5") (pintype "bidirectional"))
    )
    (net (code "72") (name "unconnected-(U5-NC-Pad6)") (class "Default")
      (node (ref "U5") (pin "6") (pinfunction "NC_6") (pintype "bidirectional"))
    )
    (net (code "73") (name "unconnected-(U5-NC-Pad7)") (class "Default")
      (node (ref "U5") (pin "7") (pinfunction "NC_7") (pintype "bidirectional"))
    )
    (net (code "74") (name "unconnected-(U5-NC-Pad14)") (class "Default")
      (node (ref "U5") (pin "14") (pinfunction "NC_14") (pintype "bidirectional"))
    )
    (net (code "75") (name "unconnected-(U6-EOC-Pad2)") (class "Default")
      (node (ref "U6") (pin "2") (pinfunction "EOC_2") (pintype "output"))
    )
    (net (code "76") (name "unconnected-(U6-NC-Pad5)") (class "Default")
      (node (ref "U6") (pin "5") (pinfunction "NC_5") (pintype "bidirectional"))
    )
    (net (code "77") (name "unconnected-(U6-XCLR-Pad8)") (class "Default")
      (node (ref "U6") (pin "8") (pinfunction "XCLR_8") (pintype "input"))
    )
  )
)
